# patch_nrd_ard.net
KiCad netlist of a schematic drawn in EAGLE
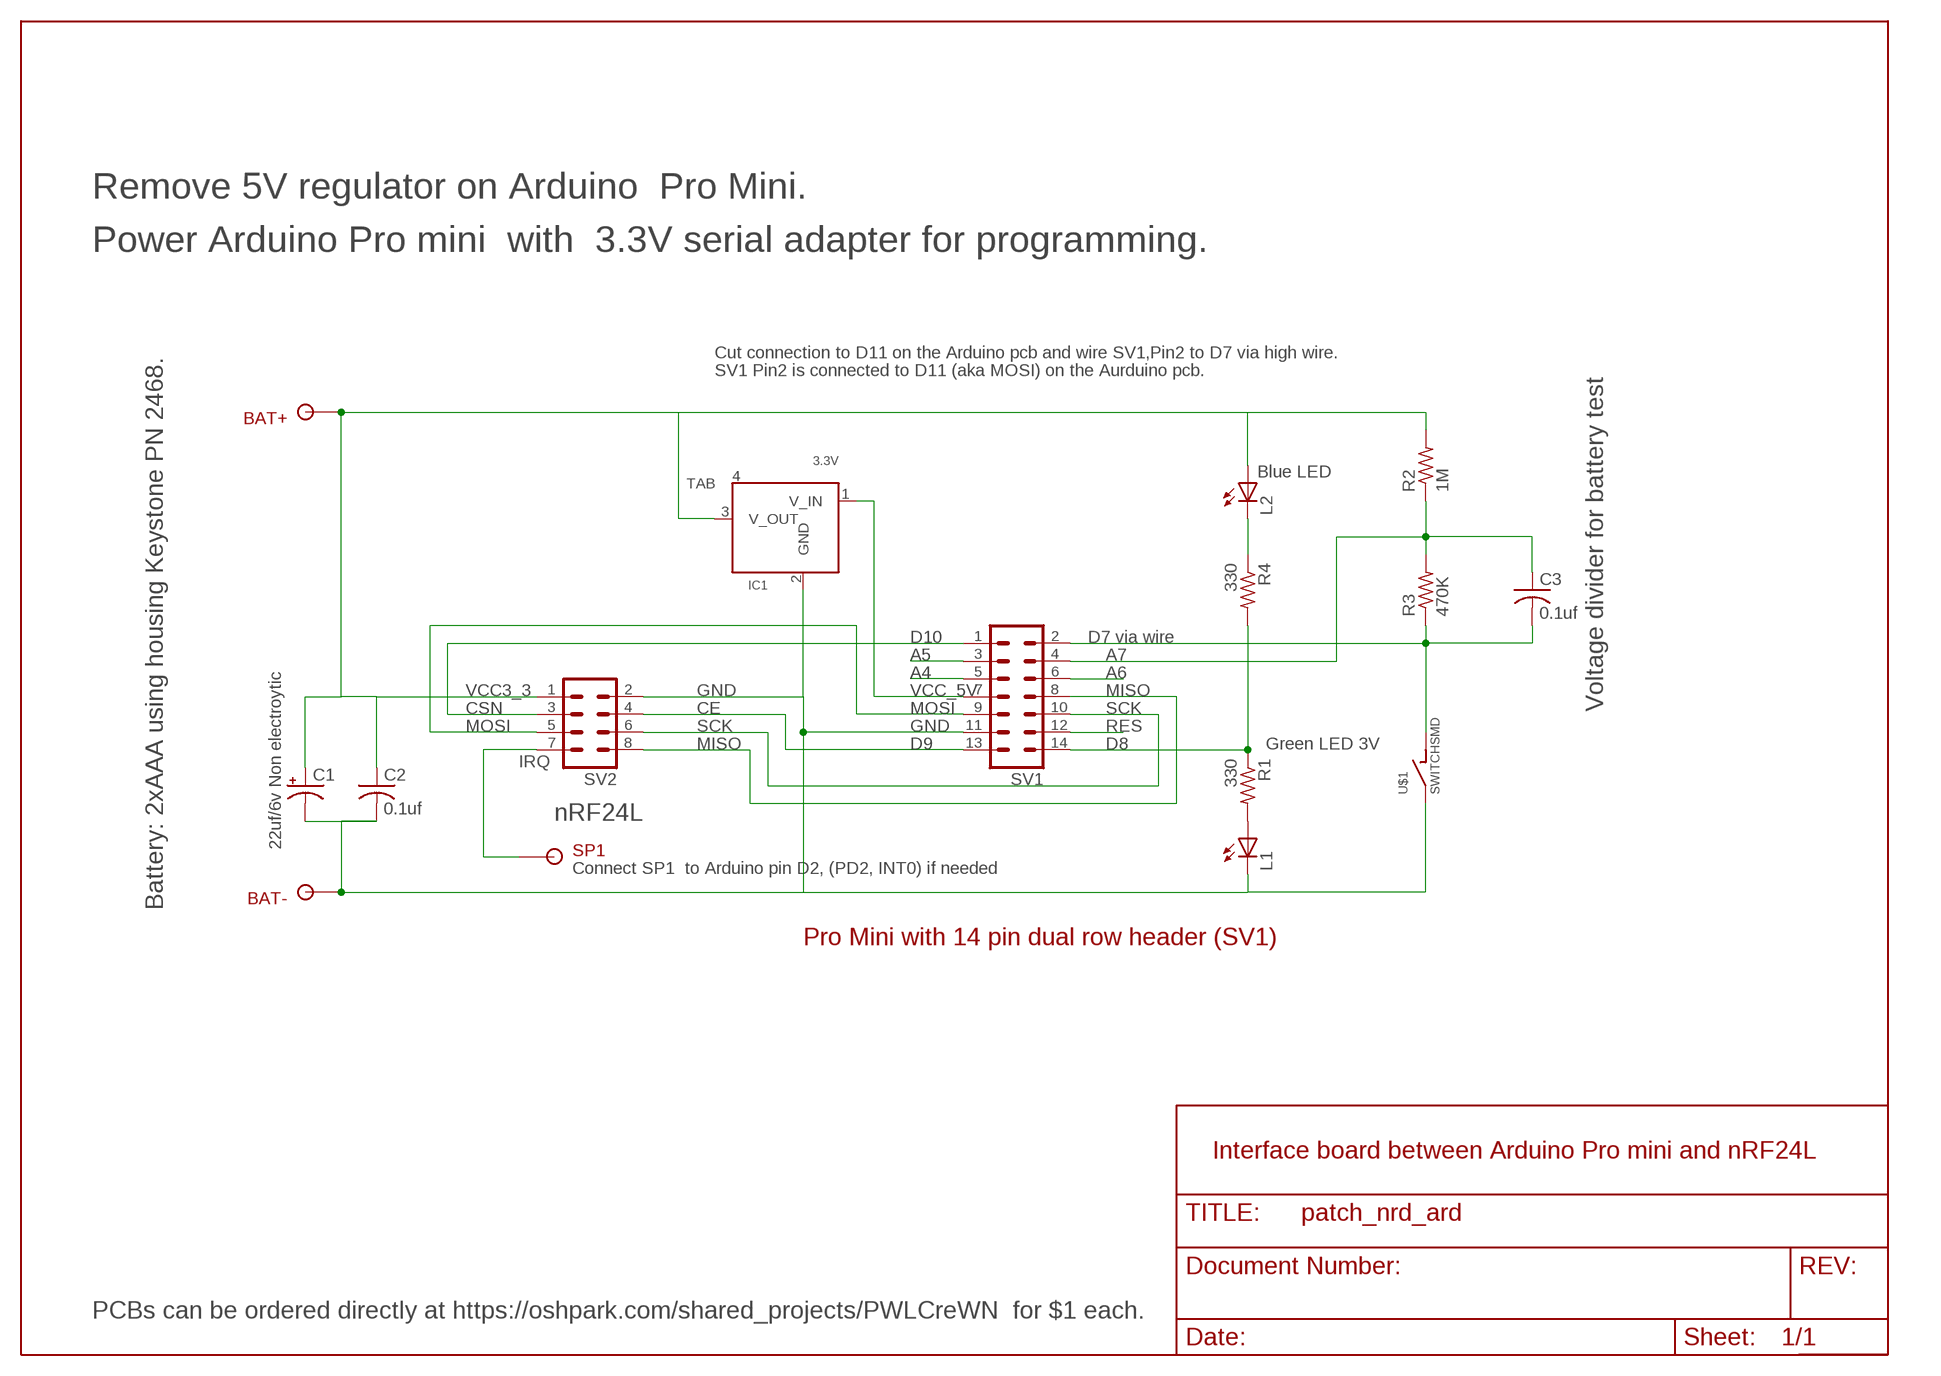
[diagram p0: schematic, sheet 1]

(export (version "E")
  (design (tool "Eeschema 10.0.6"))
  (components
    (comp (ref "BAT+")
      (value "SOLDER_POINTA")
      (footprint "eagle-import:P1-13")
      (libsource (lib "eagle-import") (part "SOLDER_POINTA"))
    )
    (comp (ref "BAT-")
      (value "SOLDER_POINTA")
      (footprint "eagle-import:P1-13")
      (libsource (lib "eagle-import") (part "SOLDER_POINTA"))
    )
    (comp (ref "C1")
      (value "22uf/6v Non electroytic")
      (footprint "eagle-import:SMC_B")
      (libsource (lib "eagle-import") (part "CPOL-USSMCB"))
    )
    (comp (ref "C2")
      (value "0.1uf")
      (footprint "eagle-import:C0805")
      (libsource (lib "eagle-import") (part "C-USC0805"))
    )
    (comp (ref "C3")
      (value "0.1uf")
      (footprint "eagle-import:C0805")
      (libsource (lib "eagle-import") (part "C-USC0805"))
    )
    (comp (ref "IC1")
      (value "3.3V")
      (footprint "eagle-import:SOT223")
      (libsource (lib "eagle-import") (part "MCP1703ASOT223"))
    )
    (comp (ref "L1")
      (value "LEDSML0603")
      (footprint "eagle-import:SML0603")
      (libsource (lib "eagle-import") (part "LEDSML0603"))
    )
    (comp (ref "L2")
      (value "LEDSML0603")
      (footprint "eagle-import:SML0603")
      (libsource (lib "eagle-import") (part "LEDSML0603"))
    )
    (comp (ref "R1")
      (value "330")
      (footprint "eagle-import:R0603")
      (libsource (lib "eagle-import") (part "R-US_R0603"))
    )
    (comp (ref "R2")
      (value "1M")
      (footprint "eagle-import:R0603")
      (libsource (lib "eagle-import") (part "R-US_R0603"))
    )
    (comp (ref "R3")
      (value "470K")
      (footprint "eagle-import:R0603")
      (libsource (lib "eagle-import") (part "R-US_R0603"))
    )
    (comp (ref "R4")
      (value "330")
      (footprint "eagle-import:R0603")
      (libsource (lib "eagle-import") (part "R-US_R0603"))
    )
    (comp (ref "SP1")
      (value "SOLDER_POINTA")
      (footprint "eagle-import:P1-13")
      (libsource (lib "eagle-import") (part "SOLDER_POINTA"))
    )
    (comp (ref "SV1")
      (value "MA07-2")
      (footprint "eagle-import:MA07-2")
      (libsource (lib "eagle-import") (part "MA07-2"))
    )
    (comp (ref "SV2")
      (value "MA04-2")
      (footprint "eagle-import:MA04-2")
      (libsource (lib "eagle-import") (part "MA04-2"))
    )
    (comp (ref "U$1")
      (value "SWITCHSMD")
      (footprint "eagle-import:SMD_SWITCH")
      (libsource (lib "eagle-import") (part "SWITCHSMD"))
    )
  )
  (nets
    (net (code "1") (name "/A4") (class "Default")
      (node (ref "SV1") (pin "5") (pinfunction "5_5") (pintype "passive"))
    )
    (net (code "2") (name "/A5") (class "Default")
      (node (ref "SV1") (pin "3") (pinfunction "3_3") (pintype "passive"))
    )
    (net (code "3") (name "/A6") (class "Default")
      (node (ref "SV1") (pin "6") (pinfunction "6_6") (pintype "passive"))
    )
    (net (code "4") (name "/A7") (class "Default")
      (node (ref "C3") (pin "1") (pinfunction "1_1") (pintype "passive"))
      (node (ref "R2") (pin "1") (pinfunction "1_1") (pintype "passive"))
      (node (ref "R3") (pin "2") (pinfunction "2_2") (pintype "passive"))
      (node (ref "SV1") (pin "4") (pinfunction "4_4") (pintype "passive"))
    )
    (net (code "5") (name "/CE") (class "Default")
      (node (ref "SV1") (pin "13") (pinfunction "13_13") (pintype "passive"))
      (node (ref "SV2") (pin "4") (pinfunction "4_4") (pintype "passive"))
    )
    (net (code "6") (name "/CSN") (class "Default")
      (node (ref "SV1") (pin "1") (pinfunction "1_1") (pintype "passive"))
      (node (ref "SV2") (pin "3") (pinfunction "3_3") (pintype "passive"))
    )
    (net (code "7") (name "/D8") (class "Default")
      (node (ref "R1") (pin "1") (pinfunction "1_1") (pintype "passive"))
      (node (ref "R4") (pin "2") (pinfunction "2_2") (pintype "passive"))
      (node (ref "SV1") (pin "14") (pinfunction "14_14") (pintype "passive"))
    )
    (net (code "8") (name "/GND") (class "Default")
      (node (ref "BAT-") (pin "1") (pinfunction "P$1_1") (pintype "bidirectional"))
      (node (ref "C1") (pin "-") (pinfunction "-_-") (pintype "passive"))
      (node (ref "C2") (pin "2") (pinfunction "2_2") (pintype "passive"))
      (node (ref "IC1") (pin "2") (pinfunction "GND_2") (pintype "bidirectional"))
      (node (ref "L1") (pin "C") (pinfunction "C_C") (pintype "passive"))
      (node (ref "SV1") (pin "11") (pinfunction "11_11") (pintype "passive"))
      (node (ref "SV2") (pin "2") (pinfunction "2_2") (pintype "passive"))
      (node (ref "U$1") (pin "P$2") (pinfunction "P$2_P$2") (pintype "passive"))
    )
    (net (code "9") (name "/IRQ") (class "Default")
      (node (ref "SP1") (pin "1") (pinfunction "P$1_1") (pintype "bidirectional"))
      (node (ref "SV2") (pin "7") (pinfunction "7_7") (pintype "passive"))
    )
    (net (code "10") (name "/MISO") (class "Default")
      (node (ref "SV1") (pin "8") (pinfunction "8_8") (pintype "passive"))
      (node (ref "SV2") (pin "8") (pinfunction "8_8") (pintype "passive"))
    )
    (net (code "11") (name "/MOSI") (class "Default")
      (node (ref "SV1") (pin "9") (pinfunction "9_9") (pintype "passive"))
      (node (ref "SV2") (pin "5") (pinfunction "5_5") (pintype "passive"))
    )
    (net (code "12") (name "/RES") (class "Default")
      (node (ref "SV1") (pin "12") (pinfunction "12_12") (pintype "passive"))
    )
    (net (code "13") (name "/SCK") (class "Default")
      (node (ref "SV1") (pin "10") (pinfunction "10_10") (pintype "passive"))
      (node (ref "SV2") (pin "6") (pinfunction "6_6") (pintype "passive"))
    )
    (net (code "14") (name "/VCC3_3") (class "Default")
      (node (ref "BAT+") (pin "1") (pinfunction "P$1_1") (pintype "bidirectional"))
      (node (ref "C1") (pin "+") (pinfunction "+_+") (pintype "passive"))
      (node (ref "C2") (pin "1") (pinfunction "1_1") (pintype "passive"))
      (node (ref "IC1") (pin "3") (pinfunction "V_OUT_3") (pintype "bidirectional"))
      (node (ref "L2") (pin "A") (pinfunction "A_A") (pintype "passive"))
      (node (ref "R2") (pin "2") (pinfunction "2_2") (pintype "passive"))
      (node (ref "SV2") (pin "1") (pinfunction "1_1") (pintype "passive"))
    )
    (net (code "15") (name "/VCC_5V") (class "Default")
      (node (ref "IC1") (pin "1") (pinfunction "V_IN_1") (pintype "bidirectional"))
      (node (ref "SV1") (pin "7") (pinfunction "7_7") (pintype "passive"))
    )
    (net (code "16") (name "Net-(C3-Pad2)") (class "Default")
      (node (ref "C3") (pin "2") (pinfunction "2_2") (pintype "passive"))
      (node (ref "R3") (pin "1") (pinfunction "1_1") (pintype "passive"))
      (node (ref "SV1") (pin "2") (pinfunction "2_2") (pintype "passive"))
      (node (ref "U$1") (pin "P$1") (pinfunction "P$1_P$1") (pintype "passive"))
    )
    (net (code "17") (name "Net-(L1-PadA)") (class "Default")
      (node (ref "L1") (pin "A") (pinfunction "A_A") (pintype "passive"))
      (node (ref "R1") (pin "2") (pinfunction "2_2") (pintype "passive"))
    )
    (net (code "18") (name "Net-(L2-PadC)") (class "Default")
      (node (ref "L2") (pin "C") (pinfunction "C_C") (pintype "passive"))
      (node (ref "R4") (pin "1") (pinfunction "1_1") (pintype "passive"))
    )
    (net (code "19") (name "unconnected-(IC1-TAB-Pad4)") (class "Default")
      (node (ref "IC1") (pin "4") (pinfunction "TAB_4") (pintype "bidirectional"))
    )
  )
)
